# Welder_HMI.net
KiCad netlist of a schematic drawn in EAGLE
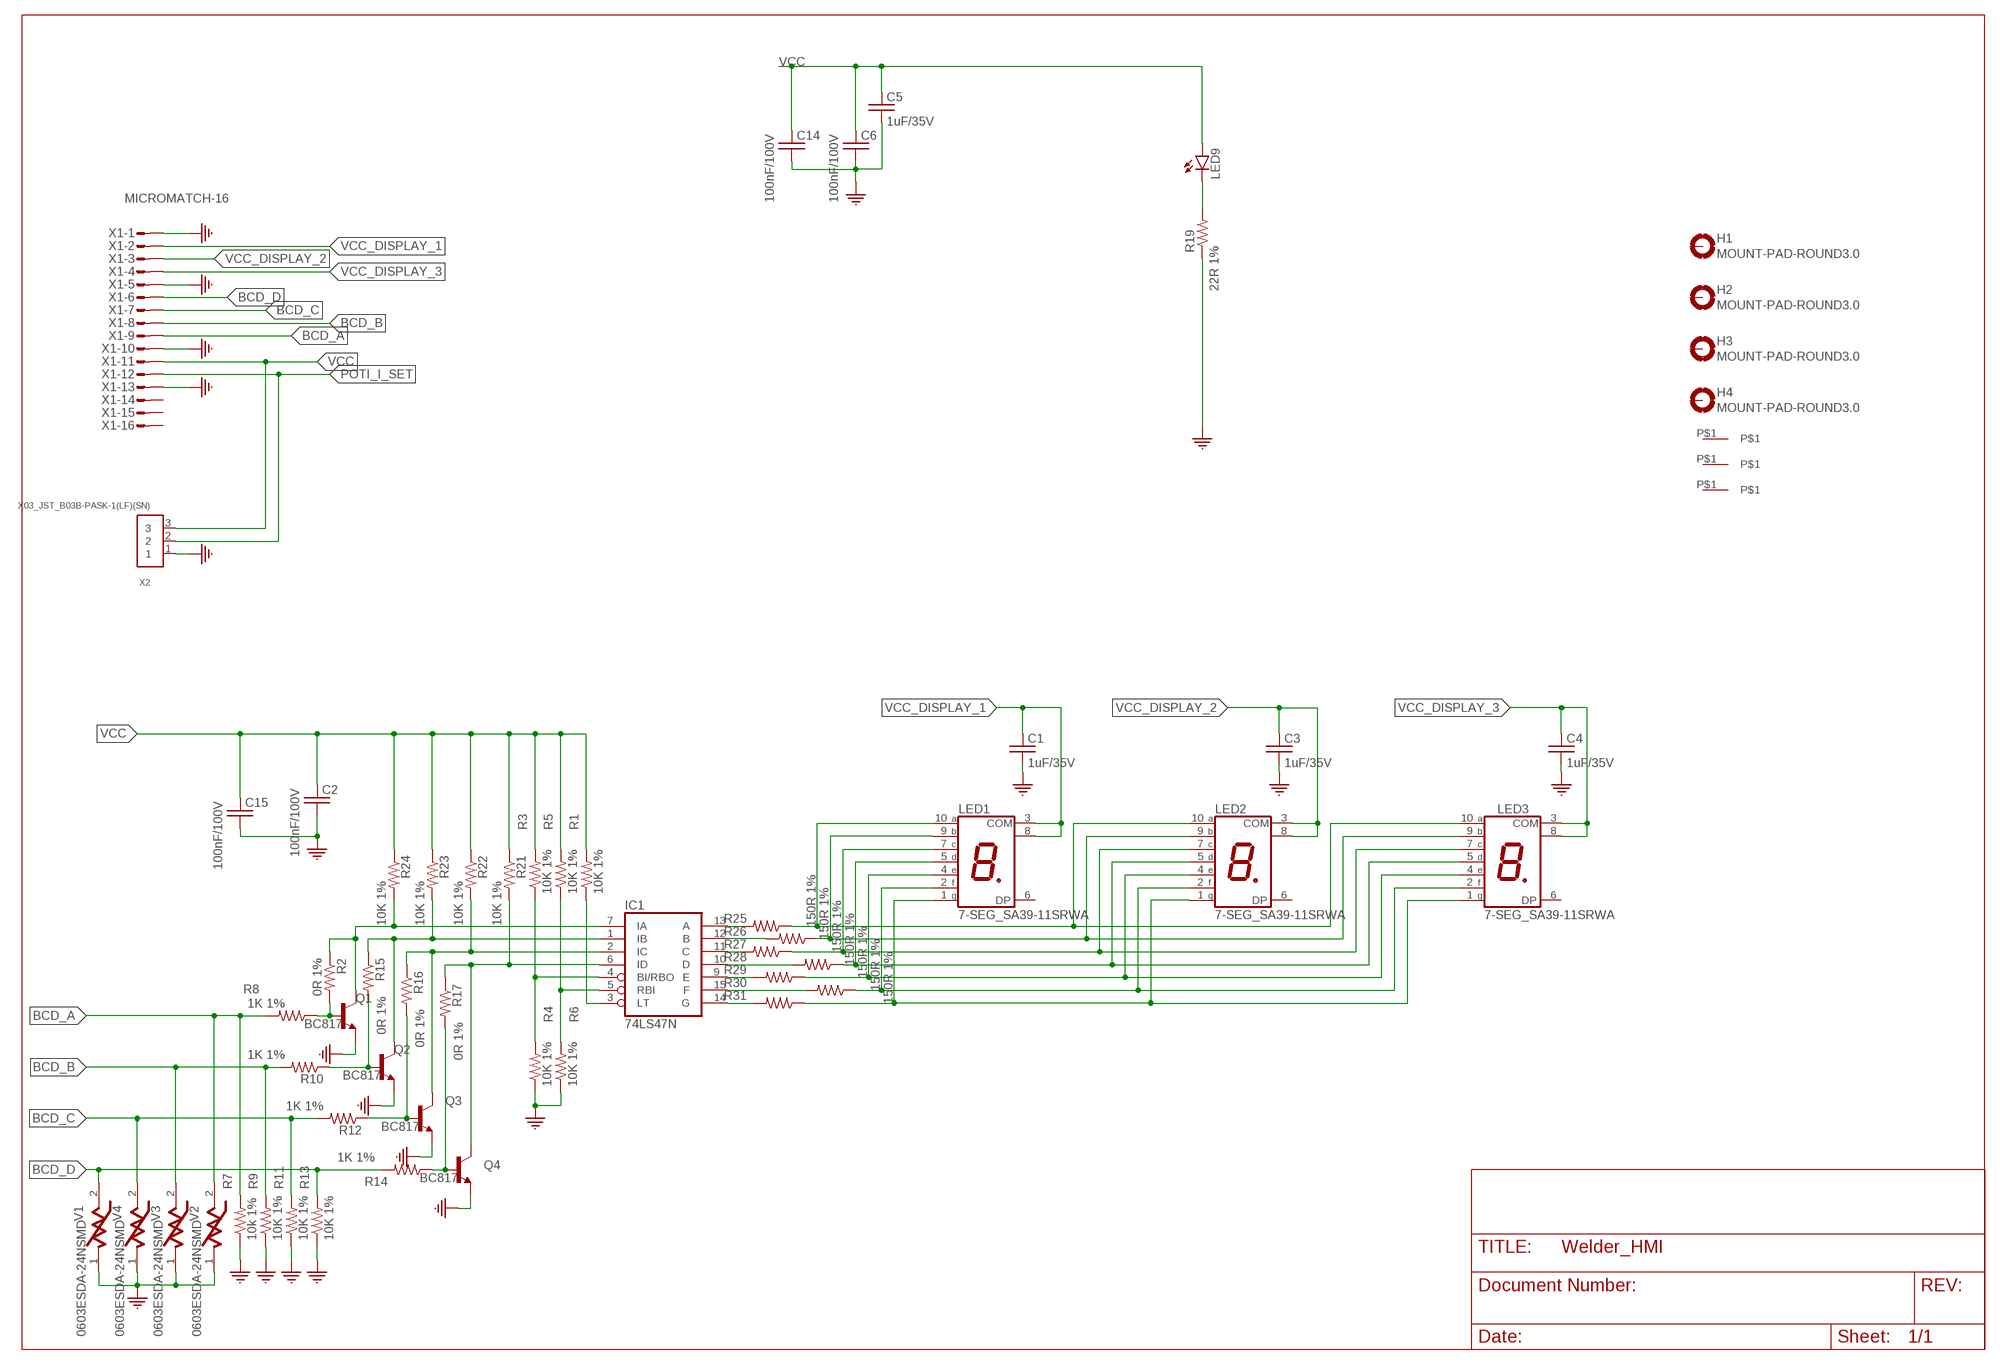
[diagram p0: schematic, sheet 1]

(export (version "E")
  (design (tool "Eeschema 10.0.6"))
  (components
    (comp (ref "C1")
      (value "1uF/35V")
      (footprint "eagle-import:EIA0603")
      (libsource (lib "eagle-import") (part "C_0603EIA0603"))
    )
    (comp (ref "C2")
      (value "100nF/100V")
      (footprint "eagle-import:EIA0603")
      (libsource (lib "eagle-import") (part "C_0603EIA0603"))
    )
    (comp (ref "C3")
      (value "1uF/35V")
      (footprint "eagle-import:EIA0603")
      (libsource (lib "eagle-import") (part "C_0603EIA0603"))
    )
    (comp (ref "C4")
      (value "1uF/35V")
      (footprint "eagle-import:EIA0603")
      (libsource (lib "eagle-import") (part "C_0603EIA0603"))
    )
    (comp (ref "C5")
      (value "1uF/35V")
      (footprint "eagle-import:EIA0603")
      (libsource (lib "eagle-import") (part "C_0603EIA0603"))
    )
    (comp (ref "C6")
      (value "100nF/100V")
      (footprint "eagle-import:EIA0603")
      (libsource (lib "eagle-import") (part "C_0603EIA0603"))
    )
    (comp (ref "C14")
      (value "100nF/100V")
      (footprint "eagle-import:EIA0603")
      (libsource (lib "eagle-import") (part "C_0603EIA0603"))
    )
    (comp (ref "C15")
      (value "100nF/100V")
      (footprint "eagle-import:EIA0603")
      (libsource (lib "eagle-import") (part "C_0603EIA0603"))
    )
    (comp (ref "FID1")
      (value "FIDUCIAL")
      (footprint "eagle-import:FIDUCIAL")
      (libsource (lib "eagle-import") (part "FIDUCIAL"))
    )
    (comp (ref "FID2")
      (value "FIDUCIAL")
      (footprint "eagle-import:FIDUCIAL")
      (libsource (lib "eagle-import") (part "FIDUCIAL"))
    )
    (comp (ref "FID3")
      (value "FIDUCIAL")
      (footprint "eagle-import:FIDUCIAL")
      (libsource (lib "eagle-import") (part "FIDUCIAL"))
    )
    (comp (ref "H1")
      (value "MOUNT-PAD-ROUND3.0")
      (footprint "eagle-import:3,0-PAD")
      (libsource (lib "eagle-import") (part "MOUNT-PAD-ROUND3.0"))
    )
    (comp (ref "H2")
      (value "MOUNT-PAD-ROUND3.0")
      (footprint "eagle-import:3,0-PAD")
      (libsource (lib "eagle-import") (part "MOUNT-PAD-ROUND3.0"))
    )
    (comp (ref "H3")
      (value "MOUNT-PAD-ROUND3.0")
      (footprint "eagle-import:3,0-PAD")
      (libsource (lib "eagle-import") (part "MOUNT-PAD-ROUND3.0"))
    )
    (comp (ref "H4")
      (value "MOUNT-PAD-ROUND3.0")
      (footprint "eagle-import:3,0-PAD")
      (libsource (lib "eagle-import") (part "MOUNT-PAD-ROUND3.0"))
    )
    (comp (ref "IC1")
      (value "74LS47N")
      (footprint "eagle-import:DIL16")
      (libsource (lib "eagle-import") (part "7447NLS"))
    )
    (comp (ref "LED1")
      (value "7-SEG_SA39-11SRWA")
      (footprint "eagle-import:SA39-11SRWA")
      (libsource (lib "eagle-import") (part "7-SEG_SA39-11SRWA"))
    )
    (comp (ref "LED2")
      (value "7-SEG_SA39-11SRWA")
      (footprint "eagle-import:SA39-11SRWA")
      (libsource (lib "eagle-import") (part "7-SEG_SA39-11SRWA"))
    )
    (comp (ref "LED3")
      (value "7-SEG_SA39-11SRWA")
      (footprint "eagle-import:SA39-11SRWA")
      (libsource (lib "eagle-import") (part "7-SEG_SA39-11SRWA"))
    )
    (comp (ref "LED9")
      (value "LED5MM")
      (footprint "eagle-import:LED5MM")
      (libsource (lib "eagle-import") (part "LED5MM"))
    )
    (comp (ref "Q1")
      (value "BC817")
      (footprint "eagle-import:SOT23")
      (fields (field (name "MFR") "NXP"))
      (libsource (lib "eagle-import") (part "BC817"))
    )
    (comp (ref "Q2")
      (value "BC817")
      (footprint "eagle-import:SOT23")
      (fields (field (name "MFR") "NXP"))
      (libsource (lib "eagle-import") (part "BC817"))
    )
    (comp (ref "Q3")
      (value "BC817")
      (footprint "eagle-import:SOT23")
      (fields (field (name "MFR") "NXP"))
      (libsource (lib "eagle-import") (part "BC817"))
    )
    (comp (ref "Q4")
      (value "BC817")
      (footprint "eagle-import:SOT23")
      (fields (field (name "MFR") "NXP"))
      (libsource (lib "eagle-import") (part "BC817"))
    )
    (comp (ref "R1")
      (value "10K 1%")
      (footprint "eagle-import:EIA0603")
      (libsource (lib "eagle-import") (part "R_0603"))
    )
    (comp (ref "R2")
      (value "0R 1%")
      (footprint "eagle-import:EIA0603")
      (libsource (lib "eagle-import") (part "R_0603"))
    )
    (comp (ref "R3")
      (value "10K 1%")
      (footprint "eagle-import:EIA0603")
      (libsource (lib "eagle-import") (part "R_0603"))
    )
    (comp (ref "R4")
      (value "10K 1%")
      (footprint "eagle-import:EIA0603")
      (libsource (lib "eagle-import") (part "R_0603"))
    )
    (comp (ref "R5")
      (value "10K 1%")
      (footprint "eagle-import:EIA0603")
      (libsource (lib "eagle-import") (part "R_0603"))
    )
    (comp (ref "R6")
      (value "10K 1%")
      (footprint "eagle-import:EIA0603")
      (libsource (lib "eagle-import") (part "R_0603"))
    )
    (comp (ref "R7")
      (value "10k 1%")
      (footprint "eagle-import:EIA0603")
      (libsource (lib "eagle-import") (part "R_0603"))
    )
    (comp (ref "R8")
      (value "1K 1%")
      (footprint "eagle-import:EIA0603")
      (libsource (lib "eagle-import") (part "R_0603"))
    )
    (comp (ref "R9")
      (value "10K 1%")
      (footprint "eagle-import:EIA0603")
      (libsource (lib "eagle-import") (part "R_0603"))
    )
    (comp (ref "R10")
      (value "1K 1%")
      (footprint "eagle-import:EIA0603")
      (libsource (lib "eagle-import") (part "R_0603"))
    )
    (comp (ref "R11")
      (value "10K 1%")
      (footprint "eagle-import:EIA0603")
      (libsource (lib "eagle-import") (part "R_0603"))
    )
    (comp (ref "R12")
      (value "1K 1%")
      (footprint "eagle-import:EIA0603")
      (libsource (lib "eagle-import") (part "R_0603"))
    )
    (comp (ref "R13")
      (value "10K 1%")
      (footprint "eagle-import:EIA0603")
      (libsource (lib "eagle-import") (part "R_0603"))
    )
    (comp (ref "R14")
      (value "1K 1%")
      (footprint "eagle-import:EIA0603")
      (libsource (lib "eagle-import") (part "R_0603"))
    )
    (comp (ref "R15")
      (value "0R 1%")
      (footprint "eagle-import:EIA0603")
      (libsource (lib "eagle-import") (part "R_0603"))
    )
    (comp (ref "R16")
      (value "0R 1%")
      (footprint "eagle-import:EIA0603")
      (libsource (lib "eagle-import") (part "R_0603"))
    )
    (comp (ref "R17")
      (value "0R 1%")
      (footprint "eagle-import:EIA0603")
      (libsource (lib "eagle-import") (part "R_0603"))
    )
    (comp (ref "R19")
      (value "22R 1%")
      (footprint "eagle-import:EIA1206")
      (libsource (lib "eagle-import") (part "R_1206EIA1206"))
    )
    (comp (ref "R21")
      (value "10K 1%")
      (footprint "eagle-import:EIA0603")
      (libsource (lib "eagle-import") (part "R_0603"))
    )
    (comp (ref "R22")
      (value "10K 1%")
      (footprint "eagle-import:EIA0603")
      (libsource (lib "eagle-import") (part "R_0603"))
    )
    (comp (ref "R23")
      (value "10K 1%")
      (footprint "eagle-import:EIA0603")
      (libsource (lib "eagle-import") (part "R_0603"))
    )
    (comp (ref "R24")
      (value "10K 1%")
      (footprint "eagle-import:EIA0603")
      (libsource (lib "eagle-import") (part "R_0603"))
    )
    (comp (ref "R25")
      (value "150R 1%")
      (footprint "eagle-import:EIA1206")
      (libsource (lib "eagle-import") (part "R_1206EIA1206"))
    )
    (comp (ref "R26")
      (value "150R 1%")
      (footprint "eagle-import:EIA1206")
      (libsource (lib "eagle-import") (part "R_1206EIA1206"))
    )
    (comp (ref "R27")
      (value "150R 1%")
      (footprint "eagle-import:EIA1206")
      (libsource (lib "eagle-import") (part "R_1206EIA1206"))
    )
    (comp (ref "R28")
      (value "150R 1%")
      (footprint "eagle-import:EIA1206")
      (libsource (lib "eagle-import") (part "R_1206EIA1206"))
    )
    (comp (ref "R29")
      (value "150R 1%")
      (footprint "eagle-import:EIA1206")
      (libsource (lib "eagle-import") (part "R_1206EIA1206"))
    )
    (comp (ref "R30")
      (value "150R 1%")
      (footprint "eagle-import:EIA1206")
      (libsource (lib "eagle-import") (part "R_1206EIA1206"))
    )
    (comp (ref "R31")
      (value "150R 1%")
      (footprint "eagle-import:EIA1206")
      (libsource (lib "eagle-import") (part "R_1206EIA1206"))
    )
    (comp (ref "V1")
      (value "0603ESDA-24NSMD")
      (footprint "eagle-import:EIA0603")
      (fields (field (name "MFR") "Bourns"))
      (libsource (lib "eagle-import") (part "0603ESDA-24NSMD"))
    )
    (comp (ref "V2")
      (value "0603ESDA-24NSMD")
      (footprint "eagle-import:EIA0603")
      (fields (field (name "MFR") "Bourns"))
      (libsource (lib "eagle-import") (part "0603ESDA-24NSMD"))
    )
    (comp (ref "V3")
      (value "0603ESDA-24NSMD")
      (footprint "eagle-import:EIA0603")
      (fields (field (name "MFR") "Bourns"))
      (libsource (lib "eagle-import") (part "0603ESDA-24NSMD"))
    )
    (comp (ref "V4")
      (value "0603ESDA-24NSMD")
      (footprint "eagle-import:EIA0603")
      (fields (field (name "MFR") "Bourns"))
      (libsource (lib "eagle-import") (part "0603ESDA-24NSMD"))
    )
    (comp (ref "X1")
      (value "MICROMATCH-16")
      (footprint "eagle-import:MICROMATCH-16")
      (fields (field (name "MF") "FARNELL") (field (name "MPN") "8-215464-6"))
      (libsource (lib "eagle-import") (part "MICROMATCH-16"))
    )
    (comp (ref "X2")
      (value "X03_JST_B03B-PASK-1(LF)(SN)")
      (footprint "eagle-import:X03_JST_B03B-PASK-1(LF)(SN)")
      (fields (field (name "MFR") "JST"))
      (libsource (lib "eagle-import") (part "X03_JST_B03B-PASK-1(LF)(SN)"))
    )
  )
  (nets
    (net (code "1") (name "BCD_A") (class "Default")
      (node (ref "R7") (pin "2") (pinfunction "2_2") (pintype "passive"))
      (node (ref "R8") (pin "2") (pinfunction "2_2") (pintype "passive"))
      (node (ref "V2") (pin "2") (pinfunction "2_2") (pintype "passive"))
      (node (ref "X1") (pin "9") (pinfunction "S_9") (pintype "passive"))
    )
    (net (code "2") (name "BCD_B") (class "Default")
      (node (ref "R10") (pin "2") (pinfunction "2_2") (pintype "passive"))
      (node (ref "R9") (pin "2") (pinfunction "2_2") (pintype "passive"))
      (node (ref "V3") (pin "2") (pinfunction "2_2") (pintype "passive"))
      (node (ref "X1") (pin "8") (pinfunction "S_8") (pintype "passive"))
    )
    (net (code "3") (name "BCD_C") (class "Default")
      (node (ref "R11") (pin "2") (pinfunction "2_2") (pintype "passive"))
      (node (ref "R12") (pin "2") (pinfunction "2_2") (pintype "passive"))
      (node (ref "V4") (pin "2") (pinfunction "2_2") (pintype "passive"))
      (node (ref "X1") (pin "7") (pinfunction "S_7") (pintype "passive"))
    )
    (net (code "4") (name "BCD_D") (class "Default")
      (node (ref "R13") (pin "2") (pinfunction "2_2") (pintype "passive"))
      (node (ref "R14") (pin "2") (pinfunction "2_2") (pintype "passive"))
      (node (ref "V1") (pin "2") (pinfunction "2_2") (pintype "passive"))
      (node (ref "X1") (pin "6") (pinfunction "S_6") (pintype "passive"))
    )
    (net (code "5") (name "GND") (class "Default")
      (node (ref "C1") (pin "2") (pinfunction "2_2") (pintype "passive"))
      (node (ref "C14") (pin "2") (pinfunction "2_2") (pintype "passive"))
      (node (ref "C15") (pin "2") (pinfunction "2_2") (pintype "passive"))
      (node (ref "C2") (pin "2") (pinfunction "2_2") (pintype "passive"))
      (node (ref "C3") (pin "2") (pinfunction "2_2") (pintype "passive"))
      (node (ref "C4") (pin "2") (pinfunction "2_2") (pintype "passive"))
      (node (ref "C5") (pin "2") (pinfunction "2_2") (pintype "passive"))
      (node (ref "C6") (pin "2") (pinfunction "2_2") (pintype "passive"))
      (node (ref "Q1") (pin "2") (pinfunction "E_2") (pintype "passive"))
      (node (ref "Q2") (pin "2") (pinfunction "E_2") (pintype "passive"))
      (node (ref "Q3") (pin "2") (pinfunction "E_2") (pintype "passive"))
      (node (ref "Q4") (pin "2") (pinfunction "E_2") (pintype "passive"))
      (node (ref "R11") (pin "1") (pinfunction "1_1") (pintype "passive"))
      (node (ref "R13") (pin "1") (pinfunction "1_1") (pintype "passive"))
      (node (ref "R19") (pin "1") (pinfunction "1_1") (pintype "passive"))
      (node (ref "R4") (pin "1") (pinfunction "1_1") (pintype "passive"))
      (node (ref "R6") (pin "1") (pinfunction "1_1") (pintype "passive"))
      (node (ref "R7") (pin "1") (pinfunction "1_1") (pintype "passive"))
      (node (ref "R9") (pin "1") (pinfunction "1_1") (pintype "passive"))
      (node (ref "V1") (pin "1") (pinfunction "1_1") (pintype "passive"))
      (node (ref "V2") (pin "1") (pinfunction "1_1") (pintype "passive"))
      (node (ref "V3") (pin "1") (pinfunction "1_1") (pintype "passive"))
      (node (ref "V4") (pin "1") (pinfunction "1_1") (pintype "passive"))
      (node (ref "X1") (pin "1") (pinfunction "S_1") (pintype "passive"))
      (node (ref "X1") (pin "10") (pinfunction "S_10") (pintype "passive"))
      (node (ref "X1") (pin "13") (pinfunction "S_13") (pintype "passive"))
      (node (ref "X1") (pin "5") (pinfunction "S_5") (pintype "passive"))
      (node (ref "X2") (pin "1") (pinfunction "1_1") (pintype "bidirectional"))
    )
    (net (code "6") (name "Net-(IC1A-A)") (class "Default")
      (node (ref "IC1") (pin "13") (pinfunction "A_13") (pintype "output"))
      (node (ref "R25") (pin "2") (pinfunction "2_2") (pintype "passive"))
    )
    (net (code "7") (name "Net-(IC1A-B)") (class "Default")
      (node (ref "IC1") (pin "12") (pinfunction "B_12") (pintype "output"))
      (node (ref "R26") (pin "2") (pinfunction "2_2") (pintype "passive"))
    )
    (net (code "8") (name "Net-(IC1A-BI{slash}RBO)") (class "Default")
      (node (ref "IC1") (pin "4") (pinfunction "BI/RBO_4") (pintype "input"))
      (node (ref "R3") (pin "1") (pinfunction "1_1") (pintype "passive"))
      (node (ref "R4") (pin "2") (pinfunction "2_2") (pintype "passive"))
    )
    (net (code "9") (name "Net-(IC1A-C)") (class "Default")
      (node (ref "IC1") (pin "11") (pinfunction "C_11") (pintype "output"))
      (node (ref "R27") (pin "2") (pinfunction "2_2") (pintype "passive"))
    )
    (net (code "10") (name "Net-(IC1A-D)") (class "Default")
      (node (ref "IC1") (pin "10") (pinfunction "D_10") (pintype "output"))
      (node (ref "R28") (pin "2") (pinfunction "2_2") (pintype "passive"))
    )
    (net (code "11") (name "Net-(IC1A-E)") (class "Default")
      (node (ref "IC1") (pin "9") (pinfunction "E_9") (pintype "output"))
      (node (ref "R29") (pin "2") (pinfunction "2_2") (pintype "passive"))
    )
    (net (code "12") (name "Net-(IC1A-F)") (class "Default")
      (node (ref "IC1") (pin "15") (pinfunction "F_15") (pintype "output"))
      (node (ref "R30") (pin "2") (pinfunction "2_2") (pintype "passive"))
    )
    (net (code "13") (name "Net-(IC1A-G)") (class "Default")
      (node (ref "IC1") (pin "14") (pinfunction "G_14") (pintype "output"))
      (node (ref "R31") (pin "2") (pinfunction "2_2") (pintype "passive"))
    )
    (net (code "14") (name "Net-(IC1A-IA)") (class "Default")
      (node (ref "IC1") (pin "7") (pinfunction "IA_7") (pintype "input"))
      (node (ref "Q1") (pin "3") (pinfunction "C_3") (pintype "passive"))
      (node (ref "R2") (pin "1") (pinfunction "1_1") (pintype "passive"))
      (node (ref "R24") (pin "2") (pinfunction "2_2") (pintype "passive"))
    )
    (net (code "15") (name "Net-(IC1A-IB)") (class "Default")
      (node (ref "IC1") (pin "1") (pinfunction "IB_1") (pintype "input"))
      (node (ref "Q2") (pin "3") (pinfunction "C_3") (pintype "passive"))
      (node (ref "R15") (pin "1") (pinfunction "1_1") (pintype "passive"))
      (node (ref "R23") (pin "2") (pinfunction "2_2") (pintype "passive"))
    )
    (net (code "16") (name "Net-(IC1A-IC)") (class "Default")
      (node (ref "IC1") (pin "2") (pinfunction "IC_2") (pintype "input"))
      (node (ref "Q3") (pin "3") (pinfunction "C_3") (pintype "passive"))
      (node (ref "R16") (pin "1") (pinfunction "1_1") (pintype "passive"))
      (node (ref "R22") (pin "2") (pinfunction "2_2") (pintype "passive"))
    )
    (net (code "17") (name "Net-(IC1A-ID)") (class "Default")
      (node (ref "IC1") (pin "6") (pinfunction "ID_6") (pintype "input"))
      (node (ref "Q4") (pin "3") (pinfunction "C_3") (pintype "passive"))
      (node (ref "R17") (pin "1") (pinfunction "1_1") (pintype "passive"))
      (node (ref "R21") (pin "2") (pinfunction "2_2") (pintype "passive"))
    )
    (net (code "18") (name "Net-(IC1A-LT)") (class "Default")
      (node (ref "IC1") (pin "3") (pinfunction "LT_3") (pintype "input"))
      (node (ref "R1") (pin "1") (pinfunction "1_1") (pintype "passive"))
    )
    (net (code "19") (name "Net-(IC1A-RBI)") (class "Default")
      (node (ref "IC1") (pin "5") (pinfunction "RBI_5") (pintype "input"))
      (node (ref "R5") (pin "1") (pinfunction "1_1") (pintype "passive"))
      (node (ref "R6") (pin "2") (pinfunction "2_2") (pintype "passive"))
    )
    (net (code "20") (name "Net-(LED1-A)") (class "Default")
      (node (ref "LED1") (pin "10") (pinfunction "A_10") (pintype "passive"))
      (node (ref "LED2") (pin "10") (pinfunction "A_10") (pintype "passive"))
      (node (ref "LED3") (pin "10") (pinfunction "A_10") (pintype "passive"))
      (node (ref "R25") (pin "1") (pinfunction "1_1") (pintype "passive"))
    )
    (net (code "21") (name "Net-(LED1-B)") (class "Default")
      (node (ref "LED1") (pin "9") (pinfunction "B_9") (pintype "passive"))
      (node (ref "LED2") (pin "9") (pinfunction "B_9") (pintype "passive"))
      (node (ref "LED3") (pin "9") (pinfunction "B_9") (pintype "passive"))
      (node (ref "R26") (pin "1") (pinfunction "1_1") (pintype "passive"))
    )
    (net (code "22") (name "Net-(LED1-C)") (class "Default")
      (node (ref "LED1") (pin "7") (pinfunction "C_7") (pintype "passive"))
      (node (ref "LED2") (pin "7") (pinfunction "C_7") (pintype "passive"))
      (node (ref "LED3") (pin "7") (pinfunction "C_7") (pintype "passive"))
      (node (ref "R27") (pin "1") (pinfunction "1_1") (pintype "passive"))
    )
    (net (code "23") (name "Net-(LED1-D)") (class "Default")
      (node (ref "LED1") (pin "5") (pinfunction "D_5") (pintype "passive"))
      (node (ref "LED2") (pin "5") (pinfunction "D_5") (pintype "passive"))
      (node (ref "LED3") (pin "5") (pinfunction "D_5") (pintype "passive"))
      (node (ref "R28") (pin "1") (pinfunction "1_1") (pintype "passive"))
    )
    (net (code "24") (name "Net-(LED1-E)") (class "Default")
      (node (ref "LED1") (pin "4") (pinfunction "E_4") (pintype "passive"))
      (node (ref "LED2") (pin "4") (pinfunction "E_4") (pintype "passive"))
      (node (ref "LED3") (pin "4") (pinfunction "E_4") (pintype "passive"))
      (node (ref "R29") (pin "1") (pinfunction "1_1") (pintype "passive"))
    )
    (net (code "25") (name "Net-(LED1-F)") (class "Default")
      (node (ref "LED1") (pin "2") (pinfunction "F_2") (pintype "passive"))
      (node (ref "LED2") (pin "2") (pinfunction "F_2") (pintype "passive"))
      (node (ref "LED3") (pin "2") (pinfunction "F_2") (pintype "passive"))
      (node (ref "R30") (pin "1") (pinfunction "1_1") (pintype "passive"))
    )
    (net (code "26") (name "Net-(LED1-G)") (class "Default")
      (node (ref "LED1") (pin "1") (pinfunction "G_1") (pintype "passive"))
      (node (ref "LED2") (pin "1") (pinfunction "G_1") (pintype "passive"))
      (node (ref "LED3") (pin "1") (pinfunction "G_1") (pintype "passive"))
      (node (ref "R31") (pin "1") (pinfunction "1_1") (pintype "passive"))
    )
    (net (code "27") (name "Net-(LED9-C)") (class "Default")
      (node (ref "LED9") (pin "K") (pinfunction "C_K") (pintype "passive"))
      (node (ref "R19") (pin "2") (pinfunction "2_2") (pintype "passive"))
    )
    (net (code "28") (name "Net-(Q1-B)") (class "Default")
      (node (ref "Q1") (pin "1") (pinfunction "B_1") (pintype "passive"))
      (node (ref "R2") (pin "2") (pinfunction "2_2") (pintype "passive"))
      (node (ref "R8") (pin "1") (pinfunction "1_1") (pintype "passive"))
    )
    (net (code "29") (name "Net-(Q2-B)") (class "Default")
      (node (ref "Q2") (pin "1") (pinfunction "B_1") (pintype "passive"))
      (node (ref "R10") (pin "1") (pinfunction "1_1") (pintype "passive"))
      (node (ref "R15") (pin "2") (pinfunction "2_2") (pintype "passive"))
    )
    (net (code "30") (name "Net-(Q3-B)") (class "Default")
      (node (ref "Q3") (pin "1") (pinfunction "B_1") (pintype "passive"))
      (node (ref "R12") (pin "1") (pinfunction "1_1") (pintype "passive"))
      (node (ref "R16") (pin "2") (pinfunction "2_2") (pintype "passive"))
    )
    (net (code "31") (name "Net-(Q4-B)") (class "Default")
      (node (ref "Q4") (pin "1") (pinfunction "B_1") (pintype "passive"))
      (node (ref "R14") (pin "1") (pinfunction "1_1") (pintype "passive"))
      (node (ref "R17") (pin "2") (pinfunction "2_2") (pintype "passive"))
    )
    (net (code "32") (name "POTI_I_SET") (class "Default")
      (node (ref "X1") (pin "12") (pinfunction "S_12") (pintype "passive"))
      (node (ref "X2") (pin "2") (pinfunction "2_2") (pintype "bidirectional"))
    )
    (net (code "33") (name "VCC") (class "Default")
      (node (ref "C14") (pin "1") (pinfunction "1_1") (pintype "passive"))
      (node (ref "C15") (pin "1") (pinfunction "1_1") (pintype "passive"))
      (node (ref "C2") (pin "1") (pinfunction "1_1") (pintype "passive"))
      (node (ref "C5") (pin "1") (pinfunction "1_1") (pintype "passive"))
      (node (ref "C6") (pin "1") (pinfunction "1_1") (pintype "passive"))
      (node (ref "LED9") (pin "A") (pinfunction "A_A") (pintype "passive"))
      (node (ref "R1") (pin "2") (pinfunction "2_2") (pintype "passive"))
      (node (ref "R21") (pin "1") (pinfunction "1_1") (pintype "passive"))
      (node (ref "R22") (pin "1") (pinfunction "1_1") (pintype "passive"))
      (node (ref "R23") (pin "1") (pinfunction "1_1") (pintype "passive"))
      (node (ref "R24") (pin "1") (pinfunction "1_1") (pintype "passive"))
      (node (ref "R3") (pin "2") (pinfunction "2_2") (pintype "passive"))
      (node (ref "R5") (pin "2") (pinfunction "2_2") (pintype "passive"))
      (node (ref "X1") (pin "11") (pinfunction "S_11") (pintype "passive"))
      (node (ref "X2") (pin "3") (pinfunction "3_3") (pintype "bidirectional"))
    )
    (net (code "34") (name "VCC_DISPLAY_1") (class "Default")
      (node (ref "C1") (pin "1") (pinfunction "1_1") (pintype "passive"))
      (node (ref "LED1") (pin "3") (pinfunction "COM_3") (pintype "passive"))
      (node (ref "LED1") (pin "8") (pinfunction "COM_8") (pintype "passive"))
      (node (ref "X1") (pin "2") (pinfunction "S_2") (pintype "passive"))
    )
    (net (code "35") (name "VCC_DISPLAY_2") (class "Default")
      (node (ref "C3") (pin "1") (pinfunction "1_1") (pintype "passive"))
      (node (ref "LED2") (pin "3") (pinfunction "COM_3") (pintype "passive"))
      (node (ref "LED2") (pin "8") (pinfunction "COM_8") (pintype "passive"))
      (node (ref "X1") (pin "3") (pinfunction "S_3") (pintype "passive"))
    )
    (net (code "36") (name "VCC_DISPLAY_3") (class "Default")
      (node (ref "C4") (pin "1") (pinfunction "1_1") (pintype "passive"))
      (node (ref "LED3") (pin "3") (pinfunction "COM_3") (pintype "passive"))
      (node (ref "LED3") (pin "8") (pinfunction "COM_8") (pintype "passive"))
      (node (ref "X1") (pin "4") (pinfunction "S_4") (pintype "passive"))
    )
    (net (code "37") (name "unconnected-(FID1-PadP$1)") (class "Default")
      (node (ref "FID1") (pin "P$1") (pinfunction "P$1_P$1") (pintype "bidirectional"))
    )
    (net (code "38") (name "unconnected-(FID2-PadP$1)") (class "Default")
      (node (ref "FID2") (pin "P$1") (pinfunction "P$1_P$1") (pintype "bidirectional"))
    )
    (net (code "39") (name "unconnected-(FID3-PadP$1)") (class "Default")
      (node (ref "FID3") (pin "P$1") (pinfunction "P$1_P$1") (pintype "bidirectional"))
    )
    (net (code "40") (name "unconnected-(H1-MOUNT-PadB3,0)") (class "Default")
      (node (ref "H1") (pin "B3,0") (pinfunction "MOUNT_B3,0") (pintype "passive"))
    )
    (net (code "41") (name "unconnected-(H2-MOUNT-PadB3,0)") (class "Default")
      (node (ref "H2") (pin "B3,0") (pinfunction "MOUNT_B3,0") (pintype "passive"))
    )
    (net (code "42") (name "unconnected-(H3-MOUNT-PadB3,0)") (class "Default")
      (node (ref "H3") (pin "B3,0") (pinfunction "MOUNT_B3,0") (pintype "passive"))
    )
    (net (code "43") (name "unconnected-(H4-MOUNT-PadB3,0)") (class "Default")
      (node (ref "H4") (pin "B3,0") (pinfunction "MOUNT_B3,0") (pintype "passive"))
    )
    (net (code "44") (name "unconnected-(LED1-DP-Pad6)") (class "Default")
      (node (ref "LED1") (pin "6") (pinfunction "DP_6") (pintype "passive"))
    )
    (net (code "45") (name "unconnected-(LED2-DP-Pad6)") (class "Default")
      (node (ref "LED2") (pin "6") (pinfunction "DP_6") (pintype "passive"))
    )
    (net (code "46") (name "unconnected-(LED3-DP-Pad6)") (class "Default")
      (node (ref "LED3") (pin "6") (pinfunction "DP_6") (pintype "passive"))
    )
    (net (code "47") (name "unconnected-(X1F-S-Pad14)") (class "Default")
      (node (ref "X1") (pin "14") (pinfunction "S_14") (pintype "passive"))
    )
    (net (code "48") (name "unconnected-(X1G-S-Pad15)") (class "Default")
      (node (ref "X1") (pin "15") (pinfunction "S_15") (pintype "passive"))
    )
    (net (code "49") (name "unconnected-(X1H-S-Pad16)") (class "Default")
      (node (ref "X1") (pin "16") (pinfunction "S_16") (pintype "passive"))
    )
  )
)
